# USB_UART.net
KiCad netlist of a schematic drawn in Altium Designer
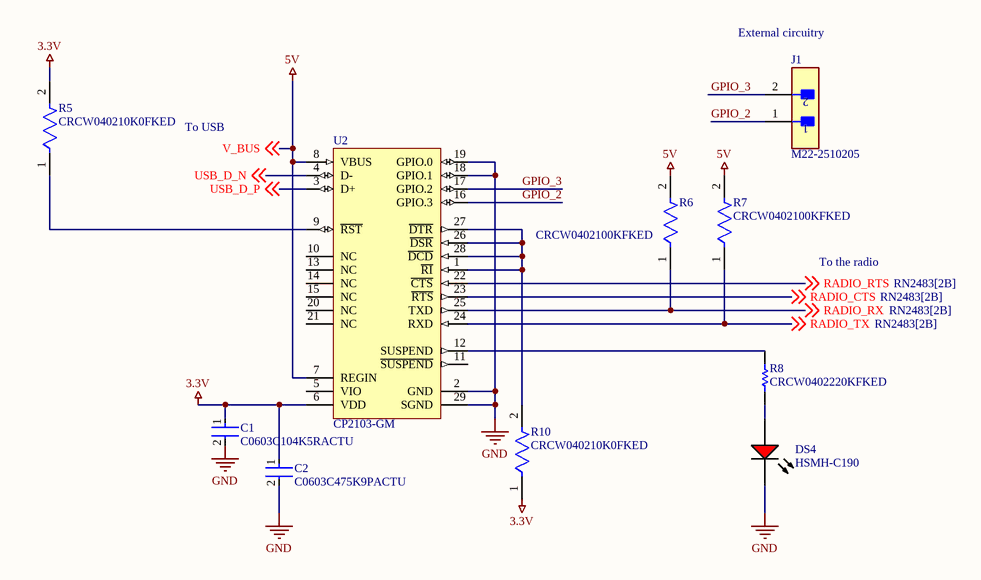
[diagram p0: USB_UART.SchDoc]

(export (version "E")
  (design (tool "Eeschema 10.0.6"))
  (components
    (comp (ref "C1")
      (value "C0603C104K5RACTU")
      (footprint "FP-C0603C-CF-MFG")
      (description "CAP CER 0.1UF 50V X7R 0603")
      (fields (field (name "TOLERANCE") "0.1") (field (name "MANUFACTURER") "KEMET"))
      (libsource (lib "Altium Content Vault") (part "b4654b650e69147ec39a6b967a45e02"))
    )
    (comp (ref "C2")
      (value "C0603C475K9PACTU")
      (footprint "FP-C0603-CG-MFG")
      (description "CAP CER 4.7UF 6.3V X5R 0603")
      (fields (field (name "TOLERANCE") "10%") (field (name "MANUFACTURER") "Kemet"))
      (libsource (lib "Altium Content Vault") (part "11868f565c42a9108669ba33697ecf6"))
    )
    (comp (ref "DS4")
      (value "HSMH-C190")
      (footprint "AVAG-HSMX-C190_V")
      (description "LED Uni-Color Red, 65 mW, 20 mA, -40 to 85 degC, 2-Pin SMD, RoHS, Tape and Reel")
      (libsource (lib "Altium Content Vault") (part "LED-RED-AK-2"))
    )
    (comp (ref "J1")
      (value "M22-2510205")
      (footprint "FP-M22-2510205-MFG")
      (description "CONN HEADER VERT 2POS 2MM")
      (fields
        (field (name "MANUFACTURER") "Harwin")
        (field (name "OCTOPART") "https://octopart.com/m22-2510205-harwin-2538221")
      )
      (libsource (lib "Altium Content Vault") (part "3bc925449376181038e59eaffc5286c"))
    )
    (comp (ref "R5")
      (value "CRCW040210K0FKED")
      (footprint "FP-CRCW0402-e3-IPC_B")
      (description "RES SMD 10K OHM 1% 1/16W 0402")
      (fields (field (name "TOLERANCE") "1%"))
      (libsource (lib "Altium Content Vault") (part "1029c3af85768c4190bb7ad29bc67b5"))
    )
    (comp (ref "R6")
      (value "CRCW0402100KFKED")
      (footprint "FP-CRCW0402-e3-IPC_C")
      (description "RES Thick Film, 100kΩ, 1%, 0.063W, 100ppm/°C, 0402")
      (fields (field (name "TOLERANCE") "1%"))
      (libsource (lib "Altium Content Vault") (part "1029c3af85768c4190bb7ad29bc67b5"))
    )
    (comp (ref "R7")
      (value "CRCW0402100KFKED")
      (footprint "FP-CRCW0402-e3-IPC_C")
      (description "RES Thick Film, 100kΩ, 1%, 0.063W, 100ppm/°C, 0402")
      (fields (field (name "TOLERANCE") "1%"))
      (libsource (lib "Altium Content Vault") (part "1029c3af85768c4190bb7ad29bc67b5"))
    )
    (comp (ref "R8")
      (value "CRCW0402220KFKED")
      (footprint "RESC1005X40X25LL05T05")
      (fields (field (name "MANUFACTURER") "Vishay Dale"))
      (libsource (lib "Altium Content Vault") (part "RES"))
    )
    (comp (ref "R10")
      (value "CRCW040210K0FKED")
      (footprint "FP-CRCW0402-e3-IPC_B")
      (description "RES SMD 10K OHM 1% 1/16W 0402")
      (fields (field (name "TOLERANCE") "1%"))
      (libsource (lib "Altium Content Vault") (part "1029c3af85768c4190bb7ad29bc67b5"))
    )
    (comp (ref "U2")
      (value "CP2103-GM")
      (footprint "SLAB-QFN-28-3125x3125TP_A_M")
      (description "Single-Chip USB to UART Bridge, 1024 Bytes EEPROM, -40 to 85 degC, 28-pin QFN, Tube")
      (fields (field (name "MANUFACTURER") "Silicon Labs"))
      (libsource (lib "Altium Content Vault") (part "SLAB-CP2103-QFN-28-29"))
    )
  )
  (nets
    (net (code "1") (name "/GPIO_2") (class "Default")
      (node (ref "J1") (pin "1") (pinfunction "1_1") (pintype "passive"))
      (node (ref "U2") (pin "16") (pinfunction "GPIO.3_16") (pintype "bidirectional"))
    )
    (net (code "2") (name "/GPIO_3") (class "Default")
      (node (ref "J1") (pin "2") (pinfunction "2_2") (pintype "passive"))
      (node (ref "U2") (pin "17") (pinfunction "GPIO.2_17") (pintype "bidirectional"))
    )
    (net (code "3") (name "3.3V") (class "Default")
      (node (ref "C1") (pin "1") (pinfunction "1_1") (pintype "passive"))
      (node (ref "C2") (pin "1") (pinfunction "1_1") (pintype "passive"))
      (node (ref "R10") (pin "1") (pinfunction "1_1") (pintype "passive"))
      (node (ref "R5") (pin "2") (pinfunction "2_2") (pintype "passive"))
      (node (ref "U2") (pin "6") (pinfunction "VDD_6") (pintype "power_in"))
    )
    (net (code "4") (name "5V") (class "Default")
      (node (ref "R6") (pin "2") (pinfunction "2_2") (pintype "passive"))
      (node (ref "R7") (pin "2") (pinfunction "2_2") (pintype "passive"))
      (node (ref "U2") (pin "7") (pinfunction "REGIN_7") (pintype "power_in"))
      (node (ref "U2") (pin "8") (pinfunction "VBUS_8") (pintype "input"))
    )
    (net (code "5") (name "GND") (class "Default")
      (node (ref "C1") (pin "2") (pinfunction "2_2") (pintype "passive"))
      (node (ref "C2") (pin "2") (pinfunction "2_2") (pintype "passive"))
      (node (ref "DS4") (pin "2") (pinfunction "K_2") (pintype "passive"))
      (node (ref "U2") (pin "18") (pinfunction "GPIO.1_18") (pintype "bidirectional"))
      (node (ref "U2") (pin "19") (pinfunction "GPIO.0_19") (pintype "bidirectional"))
      (node (ref "U2") (pin "2") (pinfunction "GND_2") (pintype "power_in"))
      (node (ref "U2") (pin "29") (pinfunction "SGND_29") (pintype "power_in"))
    )
    (net (code "6") (name "Net-(DS4-A)") (class "Default")
      (node (ref "DS4") (pin "1") (pinfunction "A_1") (pintype "passive"))
      (node (ref "R8") (pin "1") (pinfunction "1_1") (pintype "passive"))
    )
    (net (code "7") (name "Net-(U2-SUSPEND)") (class "Default")
      (node (ref "R8") (pin "2") (pinfunction "2_2") (pintype "passive"))
      (node (ref "U2") (pin "12") (pinfunction "SUSPEND_12") (pintype "output"))
    )
    (net (code "8") (name "Net-(U2-~{DCD})") (class "Default")
      (node (ref "R10") (pin "2") (pinfunction "2_2") (pintype "passive"))
      (node (ref "U2") (pin "1") (pinfunction "~{RI}_1") (pintype "input"))
      (node (ref "U2") (pin "26") (pinfunction "~{DSR}_26") (pintype "input"))
      (node (ref "U2") (pin "27") (pinfunction "~{DTR}_27") (pintype "output"))
      (node (ref "U2") (pin "28") (pinfunction "~{DCD}_28") (pintype "input"))
    )
    (net (code "9") (name "Net-(U2-~{RST})") (class "Default")
      (node (ref "R5") (pin "1") (pinfunction "1_1") (pintype "passive"))
      (node (ref "U2") (pin "9") (pinfunction "~{RST}_9") (pintype "bidirectional"))
    )
    (net (code "10") (name "RADIO_CTS") (class "Default")
      (node (ref "U2") (pin "23") (pinfunction "~{RTS}_23") (pintype "output"))
    )
    (net (code "11") (name "RADIO_RTS") (class "Default")
      (node (ref "U2") (pin "22") (pinfunction "~{CTS}_22") (pintype "input"))
    )
    (net (code "12") (name "RADIO_RX") (class "Default")
      (node (ref "R6") (pin "1") (pinfunction "1_1") (pintype "passive"))
      (node (ref "U2") (pin "25") (pinfunction "TXD_25") (pintype "output"))
    )
    (net (code "13") (name "RADIO_TX") (class "Default")
      (node (ref "R7") (pin "1") (pinfunction "1_1") (pintype "passive"))
      (node (ref "U2") (pin "24") (pinfunction "RXD_24") (pintype "input"))
    )
    (net (code "14") (name "USB_D_N") (class "Default")
      (node (ref "U2") (pin "4") (pinfunction "D-_4") (pintype "bidirectional"))
    )
    (net (code "15") (name "USB_D_P") (class "Default")
      (node (ref "U2") (pin "3") (pinfunction "D+_3") (pintype "bidirectional"))
    )
    (net (code "16") (name "unconnected-(U2-NC-Pad10)") (class "Default")
      (node (ref "U2") (pin "10") (pinfunction "NC_10") (pintype "passive"))
    )
    (net (code "17") (name "unconnected-(U2-NC-Pad13)") (class "Default")
      (node (ref "U2") (pin "13") (pinfunction "NC_13") (pintype "passive"))
    )
    (net (code "18") (name "unconnected-(U2-NC-Pad14)") (class "Default")
      (node (ref "U2") (pin "14") (pinfunction "NC_14") (pintype "passive"))
    )
    (net (code "19") (name "unconnected-(U2-NC-Pad15)") (class "Default")
      (node (ref "U2") (pin "15") (pinfunction "NC_15") (pintype "passive"))
    )
    (net (code "20") (name "unconnected-(U2-NC-Pad20)") (class "Default")
      (node (ref "U2") (pin "20") (pinfunction "NC_20") (pintype "passive"))
    )
    (net (code "21") (name "unconnected-(U2-NC-Pad21)") (class "Default")
      (node (ref "U2") (pin "21") (pinfunction "NC_21") (pintype "passive"))
    )
    (net (code "22") (name "unconnected-(U2-VIO-Pad5)") (class "Default")
      (node (ref "U2") (pin "5") (pinfunction "VIO_5") (pintype "power_in"))
    )
    (net (code "23") (name "unconnected-(U2-~{SUSPEND}-Pad11)") (class "Default")
      (node (ref "U2") (pin "11") (pinfunction "~{SUSPEND}_11") (pintype "output"))
    )
  )
)
